# 1_MCU.net
KiCad netlist of a schematic drawn in Altium Designer
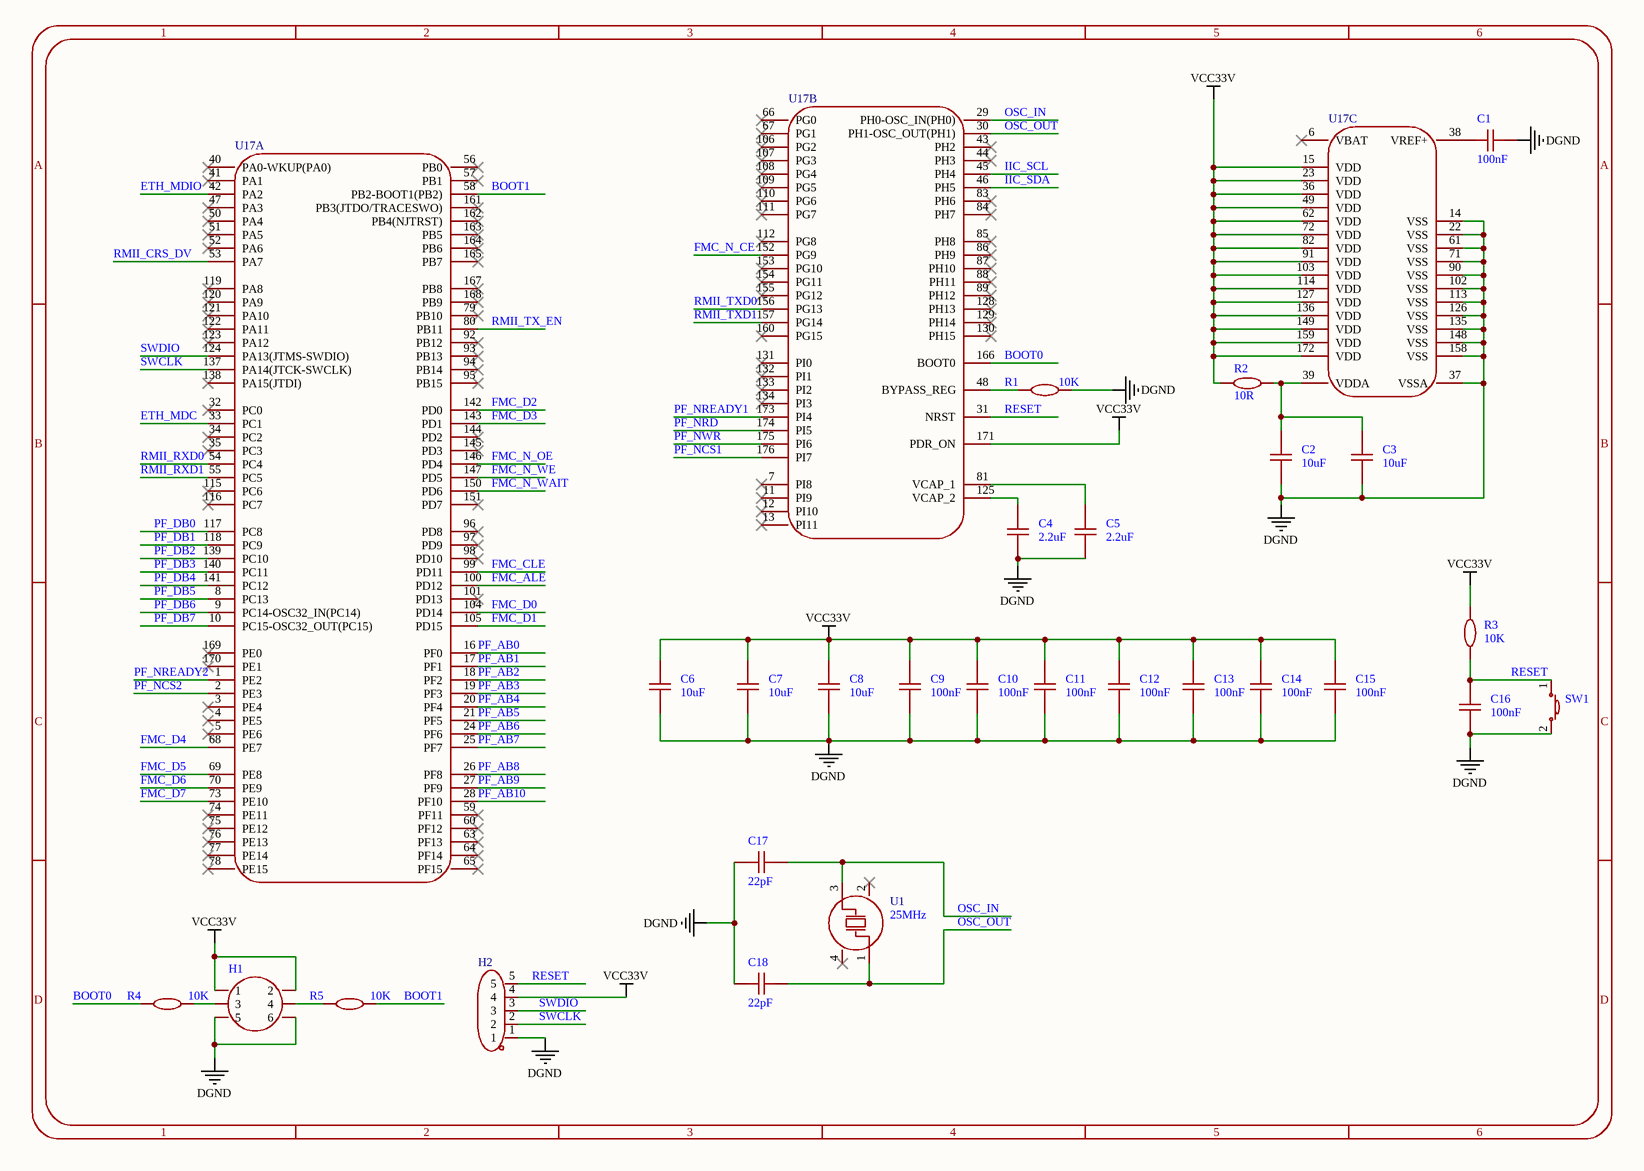
[diagram p0: 1_MCU.schdoc]

(export (version "E")
  (design (tool "Eeschema 10.0.6"))
  (components
    (comp (ref "C1")
      (value "100nF")
      (footprint "C0402")
      (libsource (lib "altium-import") (part "root_2_CAP_0402_"))
    )
    (comp (ref "C2")
      (value "10uF")
      (footprint "C0603")
      (libsource (lib "altium-import") (part "root_1_CAP_0603_"))
    )
    (comp (ref "C3")
      (value "10uF")
      (footprint "C0603")
      (libsource (lib "altium-import") (part "root_1_CAP_0603_"))
    )
    (comp (ref "C4")
      (value "2.2uF")
      (footprint "C0402")
      (libsource (lib "altium-import") (part "root_1_CAP_0402_"))
    )
    (comp (ref "C5")
      (value "2.2uF")
      (footprint "C0402")
      (libsource (lib "altium-import") (part "root_1_CAP_0402_"))
    )
    (comp (ref "C6")
      (value "10uF")
      (footprint "C0603")
      (libsource (lib "altium-import") (part "root_1_CAP_0603_"))
    )
    (comp (ref "C7")
      (value "10uF")
      (footprint "C0603")
      (libsource (lib "altium-import") (part "root_1_CAP_0603_"))
    )
    (comp (ref "C8")
      (value "10uF")
      (footprint "C0603")
      (libsource (lib "altium-import") (part "root_1_CAP_0603_"))
    )
    (comp (ref "C9")
      (value "100nF")
      (footprint "C0402")
      (libsource (lib "altium-import") (part "root_1_CAP_0402_"))
    )
    (comp (ref "C10")
      (value "100nF")
      (footprint "C0402")
      (libsource (lib "altium-import") (part "root_1_CAP_0402_"))
    )
    (comp (ref "C11")
      (value "100nF")
      (footprint "C0402")
      (libsource (lib "altium-import") (part "root_1_CAP_0402_"))
    )
    (comp (ref "C12")
      (value "100nF")
      (footprint "C0402")
      (libsource (lib "altium-import") (part "root_1_CAP_0402_"))
    )
    (comp (ref "C13")
      (value "100nF")
      (footprint "C0402")
      (libsource (lib "altium-import") (part "root_1_CAP_0402_"))
    )
    (comp (ref "C14")
      (value "100nF")
      (footprint "C0402")
      (libsource (lib "altium-import") (part "root_1_CAP_0402_"))
    )
    (comp (ref "C15")
      (value "100nF")
      (footprint "C0402")
      (libsource (lib "altium-import") (part "root_1_CAP_0402_"))
    )
    (comp (ref "C16")
      (value "100nF")
      (footprint "C0402")
      (libsource (lib "altium-import") (part "root_1_CAP_0402_"))
    )
    (comp (ref "C17")
      (value "22pF")
      (footprint "C0402")
      (libsource (lib "altium-import") (part "root_2_CAP_0402_"))
    )
    (comp (ref "C18")
      (value "22pF")
      (footprint "C0402")
      (libsource (lib "altium-import") (part "root_2_CAP_0402_"))
    )
    (comp (ref "H1")
      (value "~")
      (footprint "HDR-TH_6P-P2.54-V-R2-C3-S2.54_A2541WV-2X3P")
      (libsource (lib "altium-import") (part "root_0_HDR-M_2.54_2x3_"))
    )
    (comp (ref "H2")
      (value "~")
      (footprint "HDR-TH_5P-P2.54-V-M")
      (libsource (lib "altium-import") (part "root_2_HDR-M_2.54_1x5P_"))
    )
    (comp (ref "R1")
      (value "10K")
      (footprint "R0402")
      (libsource (lib "altium-import") (part "root_2_Res_0402_"))
    )
    (comp (ref "R2")
      (value "10R")
      (footprint "R0402")
      (libsource (lib "altium-import") (part "root_2_Res_0402_"))
    )
    (comp (ref "R3")
      (value "10K")
      (footprint "R0402")
      (libsource (lib "altium-import") (part "root_1_Res_0402_"))
    )
    (comp (ref "R4")
      (value "10K")
      (footprint "R0402")
      (libsource (lib "altium-import") (part "root_0_Res_0402_"))
    )
    (comp (ref "R5")
      (value "10K")
      (footprint "R0402")
      (libsource (lib "altium-import") (part "root_0_Res_0402_"))
    )
    (comp (ref "SW1")
      (value "~")
      (footprint "Key_SMD_3x4x2")
      (libsource (lib "altium-import") (part "root_3_Key_SMD_3x4x2_"))
    )
    (comp (ref "U1")
      (value "25MHz")
      (footprint "CRYSTAL-SMD_4P-L3.2-W2.5-TR")
      (libsource (lib "altium-import") (part "root_1_25MHz_"))
    )
    (comp (ref "U17")
      (value "~")
      (footprint "LQFP-176_L24.0-W24.0-P0.50-LS26.0-BL")
      (libsource (lib "altium-import") (part "root_0_STM32F429IGT6_"))
    )
  )
  (nets
    (net (code "1") (name "/BOOT0") (class "Default")
      (node (ref "R4") (pin "1") (pinfunction "1_1") (pintype "passive"))
      (node (ref "U17") (pin "166") (pinfunction "BOOT0_166") (pintype "passive"))
    )
    (net (code "2") (name "/BOOT1") (class "Default")
      (node (ref "R5") (pin "2") (pinfunction "2_2") (pintype "passive"))
      (node (ref "U17") (pin "58") (pinfunction "PB2-BOOT1(PB2)_58") (pintype "passive"))
    )
    (net (code "3") (name "/ETH_MDC") (class "Default")
      (node (ref "U17") (pin "33") (pinfunction "PC1_33") (pintype "passive"))
    )
    (net (code "4") (name "/ETH_MDIO") (class "Default")
      (node (ref "U17") (pin "42") (pinfunction "PA2_42") (pintype "passive"))
    )
    (net (code "5") (name "/FMC_ALE") (class "Default")
      (node (ref "U17") (pin "100") (pinfunction "PD12_100") (pintype "passive"))
    )
    (net (code "6") (name "/FMC_CLE") (class "Default")
      (node (ref "U17") (pin "99") (pinfunction "PD11_99") (pintype "passive"))
    )
    (net (code "7") (name "/FMC_D0") (class "Default")
      (node (ref "U17") (pin "104") (pinfunction "PD14_104") (pintype "passive"))
    )
    (net (code "8") (name "/FMC_D1") (class "Default")
      (node (ref "U17") (pin "105") (pinfunction "PD15_105") (pintype "passive"))
    )
    (net (code "9") (name "/FMC_D2") (class "Default")
      (node (ref "U17") (pin "142") (pinfunction "PD0_142") (pintype "passive"))
    )
    (net (code "10") (name "/FMC_D3") (class "Default")
      (node (ref "U17") (pin "143") (pinfunction "PD1_143") (pintype "passive"))
    )
    (net (code "11") (name "/FMC_D4") (class "Default")
      (node (ref "U17") (pin "68") (pinfunction "PE7_68") (pintype "passive"))
    )
    (net (code "12") (name "/FMC_D5") (class "Default")
      (node (ref "U17") (pin "69") (pinfunction "PE8_69") (pintype "passive"))
    )
    (net (code "13") (name "/FMC_D6") (class "Default")
      (node (ref "U17") (pin "70") (pinfunction "PE9_70") (pintype "passive"))
    )
    (net (code "14") (name "/FMC_D7") (class "Default")
      (node (ref "U17") (pin "73") (pinfunction "PE10_73") (pintype "passive"))
    )
    (net (code "15") (name "/FMC_N_CE") (class "Default")
      (node (ref "U17") (pin "152") (pinfunction "PG9_152") (pintype "passive"))
    )
    (net (code "16") (name "/FMC_N_OE") (class "Default")
      (node (ref "U17") (pin "146") (pinfunction "PD4_146") (pintype "passive"))
    )
    (net (code "17") (name "/FMC_N_WAIT") (class "Default")
      (node (ref "U17") (pin "150") (pinfunction "PD6_150") (pintype "passive"))
    )
    (net (code "18") (name "/FMC_N_WE") (class "Default")
      (node (ref "U17") (pin "147") (pinfunction "PD5_147") (pintype "passive"))
    )
    (net (code "19") (name "/IIC_SCL") (class "Default")
      (node (ref "U17") (pin "45") (pinfunction "PH4_45") (pintype "passive"))
    )
    (net (code "20") (name "/IIC_SDA") (class "Default")
      (node (ref "U17") (pin "46") (pinfunction "PH5_46") (pintype "passive"))
    )
    (net (code "21") (name "/OSC_IN") (class "Default")
      (node (ref "C17") (pin "1") (pinfunction "1_1") (pintype "passive"))
      (node (ref "U1") (pin "3") (pinfunction "OSC2_3") (pintype "passive"))
      (node (ref "U17") (pin "29") (pinfunction "PH0-OSC_IN(PH0)_29") (pintype "passive"))
    )
    (net (code "22") (name "/OSC_OUT") (class "Default")
      (node (ref "C18") (pin "1") (pinfunction "1_1") (pintype "passive"))
      (node (ref "U1") (pin "1") (pinfunction "OSC1_1") (pintype "passive"))
      (node (ref "U17") (pin "30") (pinfunction "PH1-OSC_OUT(PH1)_30") (pintype "passive"))
    )
    (net (code "23") (name "/PF_AB0") (class "Default")
      (node (ref "U17") (pin "16") (pinfunction "PF0_16") (pintype "passive"))
    )
    (net (code "24") (name "/PF_AB1") (class "Default")
      (node (ref "U17") (pin "17") (pinfunction "PF1_17") (pintype "passive"))
    )
    (net (code "25") (name "/PF_AB2") (class "Default")
      (node (ref "U17") (pin "18") (pinfunction "PF2_18") (pintype "passive"))
    )
    (net (code "26") (name "/PF_AB3") (class "Default")
      (node (ref "U17") (pin "19") (pinfunction "PF3_19") (pintype "passive"))
    )
    (net (code "27") (name "/PF_AB4") (class "Default")
      (node (ref "U17") (pin "20") (pinfunction "PF4_20") (pintype "passive"))
    )
    (net (code "28") (name "/PF_AB5") (class "Default")
      (node (ref "U17") (pin "21") (pinfunction "PF5_21") (pintype "passive"))
    )
    (net (code "29") (name "/PF_AB6") (class "Default")
      (node (ref "U17") (pin "24") (pinfunction "PF6_24") (pintype "passive"))
    )
    (net (code "30") (name "/PF_AB7") (class "Default")
      (node (ref "U17") (pin "25") (pinfunction "PF7_25") (pintype "passive"))
    )
    (net (code "31") (name "/PF_AB8") (class "Default")
      (node (ref "U17") (pin "26") (pinfunction "PF8_26") (pintype "passive"))
    )
    (net (code "32") (name "/PF_AB9") (class "Default")
      (node (ref "U17") (pin "27") (pinfunction "PF9_27") (pintype "passive"))
    )
    (net (code "33") (name "/PF_AB10") (class "Default")
      (node (ref "U17") (pin "28") (pinfunction "PF10_28") (pintype "passive"))
    )
    (net (code "34") (name "/PF_DB0") (class "Default")
      (node (ref "U17") (pin "117") (pinfunction "PC8_117") (pintype "passive"))
    )
    (net (code "35") (name "/PF_DB1") (class "Default")
      (node (ref "U17") (pin "118") (pinfunction "PC9_118") (pintype "passive"))
    )
    (net (code "36") (name "/PF_DB2") (class "Default")
      (node (ref "U17") (pin "139") (pinfunction "PC10_139") (pintype "passive"))
    )
    (net (code "37") (name "/PF_DB3") (class "Default")
      (node (ref "U17") (pin "140") (pinfunction "PC11_140") (pintype "passive"))
    )
    (net (code "38") (name "/PF_DB4") (class "Default")
      (node (ref "U17") (pin "141") (pinfunction "PC12_141") (pintype "passive"))
    )
    (net (code "39") (name "/PF_DB5") (class "Default")
      (node (ref "U17") (pin "8") (pinfunction "PC13_8") (pintype "passive"))
    )
    (net (code "40") (name "/PF_DB6") (class "Default")
      (node (ref "U17") (pin "9") (pinfunction "PC14-OSC32_IN(PC14)_9") (pintype "passive"))
    )
    (net (code "41") (name "/PF_DB7") (class "Default")
      (node (ref "U17") (pin "10") (pinfunction "PC15-OSC32_OUT(PC15)_10") (pintype "passive"))
    )
    (net (code "42") (name "/PF_NCS1") (class "Default")
      (node (ref "U17") (pin "176") (pinfunction "PI7_176") (pintype "passive"))
    )
    (net (code "43") (name "/PF_NCS2") (class "Default")
      (node (ref "U17") (pin "2") (pinfunction "PE3_2") (pintype "passive"))
    )
    (net (code "44") (name "/PF_NRD") (class "Default")
      (node (ref "U17") (pin "174") (pinfunction "PI5_174") (pintype "passive"))
    )
    (net (code "45") (name "/PF_NREADY1") (class "Default")
      (node (ref "U17") (pin "173") (pinfunction "PI4_173") (pintype "passive"))
    )
    (net (code "46") (name "/PF_NREADY2") (class "Default")
      (node (ref "U17") (pin "1") (pinfunction "PE2_1") (pintype "passive"))
    )
    (net (code "47") (name "/PF_NWR") (class "Default")
      (node (ref "U17") (pin "175") (pinfunction "PI6_175") (pintype "passive"))
    )
    (net (code "48") (name "/RESET") (class "Default")
      (node (ref "C16") (pin "2") (pinfunction "2_2") (pintype "passive"))
      (node (ref "H2") (pin "5") (pinfunction "5_5") (pintype "passive"))
      (node (ref "R3") (pin "1") (pinfunction "1_1") (pintype "passive"))
      (node (ref "SW1") (pin "1") (pinfunction "1_1") (pintype "passive"))
      (node (ref "U17") (pin "31") (pinfunction "NRST_31") (pintype "passive"))
    )
    (net (code "49") (name "/RMII_CRS_DV") (class "Default")
      (node (ref "U17") (pin "53") (pinfunction "PA7_53") (pintype "passive"))
    )
    (net (code "50") (name "/RMII_RXD0") (class "Default")
      (node (ref "U17") (pin "54") (pinfunction "PC4_54") (pintype "passive"))
    )
    (net (code "51") (name "/RMII_RXD1") (class "Default")
      (node (ref "U17") (pin "55") (pinfunction "PC5_55") (pintype "passive"))
    )
    (net (code "52") (name "/RMII_TXD0") (class "Default")
      (node (ref "U17") (pin "156") (pinfunction "PG13_156") (pintype "passive"))
    )
    (net (code "53") (name "/RMII_TXD1") (class "Default")
      (node (ref "U17") (pin "157") (pinfunction "PG14_157") (pintype "passive"))
    )
    (net (code "54") (name "/RMII_TX_EN") (class "Default")
      (node (ref "U17") (pin "80") (pinfunction "PB11_80") (pintype "passive"))
    )
    (net (code "55") (name "/SWCLK") (class "Default")
      (node (ref "H2") (pin "2") (pinfunction "2_2") (pintype "passive"))
      (node (ref "U17") (pin "137") (pinfunction "PA14(JTCK-SWCLK)_137") (pintype "passive"))
    )
    (net (code "56") (name "/SWDIO") (class "Default")
      (node (ref "H2") (pin "3") (pinfunction "3_3") (pintype "passive"))
      (node (ref "U17") (pin "124") (pinfunction "PA13(JTMS-SWDIO)_124") (pintype "passive"))
    )
    (net (code "57") (name "DGND") (class "Default")
      (node (ref "C1") (pin "1") (pinfunction "1_1") (pintype "passive"))
      (node (ref "C10") (pin "1") (pinfunction "1_1") (pintype "passive"))
      (node (ref "C11") (pin "1") (pinfunction "1_1") (pintype "passive"))
      (node (ref "C12") (pin "1") (pinfunction "1_1") (pintype "passive"))
      (node (ref "C13") (pin "1") (pinfunction "1_1") (pintype "passive"))
      (node (ref "C14") (pin "1") (pinfunction "1_1") (pintype "passive"))
      (node (ref "C15") (pin "1") (pinfunction "1_1") (pintype "passive"))
      (node (ref "C16") (pin "1") (pinfunction "1_1") (pintype "passive"))
      (node (ref "C17") (pin "2") (pinfunction "2_2") (pintype "passive"))
      (node (ref "C18") (pin "2") (pinfunction "2_2") (pintype "passive"))
      (node (ref "C2") (pin "1") (pinfunction "1_1") (pintype "passive"))
      (node (ref "C3") (pin "1") (pinfunction "1_1") (pintype "passive"))
      (node (ref "C4") (pin "1") (pinfunction "1_1") (pintype "passive"))
      (node (ref "C5") (pin "1") (pinfunction "1_1") (pintype "passive"))
      (node (ref "C6") (pin "1") (pinfunction "1_1") (pintype "passive"))
      (node (ref "C7") (pin "1") (pinfunction "1_1") (pintype "passive"))
      (node (ref "C8") (pin "1") (pinfunction "1_1") (pintype "passive"))
      (node (ref "C9") (pin "1") (pinfunction "1_1") (pintype "passive"))
      (node (ref "H1") (pin "5") (pinfunction "5_5") (pintype "passive"))
      (node (ref "H1") (pin "6") (pinfunction "6_6") (pintype "passive"))
      (node (ref "H2") (pin "1") (pinfunction "1_1") (pintype "passive"))
      (node (ref "R1") (pin "1") (pinfunction "1_1") (pintype "passive"))
      (node (ref "SW1") (pin "2") (pinfunction "2_2") (pintype "passive"))
      (node (ref "U17") (pin "102") (pinfunction "VSS_102") (pintype "passive"))
      (node (ref "U17") (pin "113") (pinfunction "VSS_113") (pintype "passive"))
      (node (ref "U17") (pin "126") (pinfunction "VSS_126") (pintype "passive"))
      (node (ref "U17") (pin "135") (pinfunction "VSS_135") (pintype "passive"))
      (node (ref "U17") (pin "14") (pinfunction "VSS_14") (pintype "passive"))
      (node (ref "U17") (pin "148") (pinfunction "VSS_148") (pintype "passive"))
      (node (ref "U17") (pin "158") (pinfunction "VSS_158") (pintype "passive"))
      (node (ref "U17") (pin "22") (pinfunction "VSS_22") (pintype "passive"))
      (node (ref "U17") (pin "37") (pinfunction "VSSA_37") (pintype "passive"))
      (node (ref "U17") (pin "61") (pinfunction "VSS_61") (pintype "passive"))
      (node (ref "U17") (pin "71") (pinfunction "VSS_71") (pintype "passive"))
      (node (ref "U17") (pin "90") (pinfunction "VSS_90") (pintype "passive"))
    )
    (net (code "58") (name "Net-(H1-Pad3)") (class "Default")
      (node (ref "H1") (pin "3") (pinfunction "3_3") (pintype "passive"))
      (node (ref "R4") (pin "2") (pinfunction "2_2") (pintype "passive"))
    )
    (net (code "59") (name "Net-(H1-Pad4)") (class "Default")
      (node (ref "H1") (pin "4") (pinfunction "4_4") (pintype "passive"))
      (node (ref "R5") (pin "1") (pinfunction "1_1") (pintype "passive"))
    )
    (net (code "60") (name "Net-(U17B-BYPASS_REG)") (class "Default")
      (node (ref "R1") (pin "2") (pinfunction "2_2") (pintype "passive"))
      (node (ref "U17") (pin "48") (pinfunction "BYPASS_REG_48") (pintype "passive"))
    )
    (net (code "61") (name "Net-(U17B-VCAP_1)") (class "Default")
      (node (ref "C5") (pin "2") (pinfunction "2_2") (pintype "passive"))
      (node (ref "U17") (pin "81") (pinfunction "VCAP_1_81") (pintype "passive"))
    )
    (net (code "62") (name "Net-(U17B-VCAP_2)") (class "Default")
      (node (ref "C4") (pin "2") (pinfunction "2_2") (pintype "passive"))
      (node (ref "U17") (pin "125") (pinfunction "VCAP_2_125") (pintype "passive"))
    )
    (net (code "63") (name "Net-(U17C-VDDA)") (class "Default")
      (node (ref "C2") (pin "2") (pinfunction "2_2") (pintype "passive"))
      (node (ref "C3") (pin "2") (pinfunction "2_2") (pintype "passive"))
      (node (ref "R2") (pin "1") (pinfunction "1_1") (pintype "passive"))
      (node (ref "U17") (pin "39") (pinfunction "VDDA_39") (pintype "passive"))
    )
    (net (code "64") (name "Net-(U17C-VREF+)") (class "Default")
      (node (ref "C1") (pin "2") (pinfunction "2_2") (pintype "passive"))
      (node (ref "U17") (pin "38") (pinfunction "VREF+_38") (pintype "passive"))
    )
    (net (code "65") (name "VCC33V") (class "Default")
      (node (ref "C10") (pin "2") (pinfunction "2_2") (pintype "passive"))
      (node (ref "C11") (pin "2") (pinfunction "2_2") (pintype "passive"))
      (node (ref "C12") (pin "2") (pinfunction "2_2") (pintype "passive"))
      (node (ref "C13") (pin "2") (pinfunction "2_2") (pintype "passive"))
      (node (ref "C14") (pin "2") (pinfunction "2_2") (pintype "passive"))
      (node (ref "C15") (pin "2") (pinfunction "2_2") (pintype "passive"))
      (node (ref "C6") (pin "2") (pinfunction "2_2") (pintype "passive"))
      (node (ref "C7") (pin "2") (pinfunction "2_2") (pintype "passive"))
      (node (ref "C8") (pin "2") (pinfunction "2_2") (pintype "passive"))
      (node (ref "C9") (pin "2") (pinfunction "2_2") (pintype "passive"))
      (node (ref "H1") (pin "1") (pinfunction "1_1") (pintype "passive"))
      (node (ref "H1") (pin "2") (pinfunction "2_2") (pintype "passive"))
      (node (ref "H2") (pin "4") (pinfunction "4_4") (pintype "passive"))
      (node (ref "R2") (pin "2") (pinfunction "2_2") (pintype "passive"))
      (node (ref "R3") (pin "2") (pinfunction "2_2") (pintype "passive"))
      (node (ref "U17") (pin "103") (pinfunction "VDD_103") (pintype "passive"))
      (node (ref "U17") (pin "114") (pinfunction "VDD_114") (pintype "passive"))
      (node (ref "U17") (pin "127") (pinfunction "VDD_127") (pintype "passive"))
      (node (ref "U17") (pin "136") (pinfunction "VDD_136") (pintype "passive"))
      (node (ref "U17") (pin "149") (pinfunction "VDD_149") (pintype "passive"))
      (node (ref "U17") (pin "15") (pinfunction "VDD_15") (pintype "passive"))
      (node (ref "U17") (pin "159") (pinfunction "VDD_159") (pintype "passive"))
      (node (ref "U17") (pin "171") (pinfunction "PDR_ON_171") (pintype "passive"))
      (node (ref "U17") (pin "172") (pinfunction "VDD_172") (pintype "passive"))
      (node (ref "U17") (pin "23") (pinfunction "VDD_23") (pintype "passive"))
      (node (ref "U17") (pin "36") (pinfunction "VDD_36") (pintype "passive"))
      (node (ref "U17") (pin "49") (pinfunction "VDD_49") (pintype "passive"))
      (node (ref "U17") (pin "62") (pinfunction "VDD_62") (pintype "passive"))
      (node (ref "U17") (pin "72") (pinfunction "VDD_72") (pintype "passive"))
      (node (ref "U17") (pin "82") (pinfunction "VDD_82") (pintype "passive"))
      (node (ref "U17") (pin "91") (pinfunction "VDD_91") (pintype "passive"))
    )
    (net (code "66") (name "unconnected-(U1-GND-Pad2)") (class "Default")
      (node (ref "U1") (pin "2") (pinfunction "GND_2") (pintype "passive+no_connect"))
    )
    (net (code "67") (name "unconnected-(U1-GND-Pad4)") (class "Default")
      (node (ref "U1") (pin "4") (pinfunction "GND_4") (pintype "passive+no_connect"))
    )
    (net (code "68") (name "unconnected-(U17A-PA0-WKUP(PA0)-Pad40)") (class "Default")
      (node (ref "U17") (pin "40") (pinfunction "PA0-WKUP(PA0)_40") (pintype "passive+no_connect"))
    )
    (net (code "69") (name "unconnected-(U17A-PA1-Pad41)") (class "Default")
      (node (ref "U17") (pin "41") (pinfunction "PA1_41") (pintype "passive+no_connect"))
    )
    (net (code "70") (name "unconnected-(U17A-PA3-Pad47)") (class "Default")
      (node (ref "U17") (pin "47") (pinfunction "PA3_47") (pintype "passive+no_connect"))
    )
    (net (code "71") (name "unconnected-(U17A-PA4-Pad50)") (class "Default")
      (node (ref "U17") (pin "50") (pinfunction "PA4_50") (pintype "passive+no_connect"))
    )
    (net (code "72") (name "unconnected-(U17A-PA5-Pad51)") (class "Default")
      (node (ref "U17") (pin "51") (pinfunction "PA5_51") (pintype "passive+no_connect"))
    )
    (net (code "73") (name "unconnected-(U17A-PA6-Pad52)") (class "Default")
      (node (ref "U17") (pin "52") (pinfunction "PA6_52") (pintype "passive+no_connect"))
    )
    (net (code "74") (name "unconnected-(U17A-PA8-Pad119)") (class "Default")
      (node (ref "U17") (pin "119") (pinfunction "PA8_119") (pintype "passive+no_connect"))
    )
    (net (code "75") (name "unconnected-(U17A-PA9-Pad120)") (class "Default")
      (node (ref "U17") (pin "120") (pinfunction "PA9_120") (pintype "passive+no_connect"))
    )
    (net (code "76") (name "unconnected-(U17A-PA10-Pad121)") (class "Default")
      (node (ref "U17") (pin "121") (pinfunction "PA10_121") (pintype "passive+no_connect"))
    )
    (net (code "77") (name "unconnected-(U17A-PA11-Pad122)") (class "Default")
      (node (ref "U17") (pin "122") (pinfunction "PA11_122") (pintype "passive+no_connect"))
    )
    (net (code "78") (name "unconnected-(U17A-PA12-Pad123)") (class "Default")
      (node (ref "U17") (pin "123") (pinfunction "PA12_123") (pintype "passive+no_connect"))
    )
    (net (code "79") (name "unconnected-(U17A-PA15(JTDI)-Pad138)") (class "Default")
      (node (ref "U17") (pin "138") (pinfunction "PA15(JTDI)_138") (pintype "passive+no_connect"))
    )
    (net (code "80") (name "unconnected-(U17A-PB0-Pad56)") (class "Default")
      (node (ref "U17") (pin "56") (pinfunction "PB0_56") (pintype "passive+no_connect"))
    )
    (net (code "81") (name "unconnected-(U17A-PB1-Pad57)") (class "Default")
      (node (ref "U17") (pin "57") (pinfunction "PB1_57") (pintype "passive+no_connect"))
    )
    (net (code "82") (name "unconnected-(U17A-PB3(JTDO{slash}TRACESWO)-Pad161)") (class "Default")
      (node (ref "U17") (pin "161") (pinfunction "PB3(JTDO/TRACESWO)_161") (pintype "passive+no_connect"))
    )
    (net (code "83") (name "unconnected-(U17A-PB4(NJTRST)-Pad162)") (class "Default")
      (node (ref "U17") (pin "162") (pinfunction "PB4(NJTRST)_162") (pintype "passive+no_connect"))
    )
    (net (code "84") (name "unconnected-(U17A-PB5-Pad163)") (class "Default")
      (node (ref "U17") (pin "163") (pinfunction "PB5_163") (pintype "passive+no_connect"))
    )
    (net (code "85") (name "unconnected-(U17A-PB6-Pad164)") (class "Default")
      (node (ref "U17") (pin "164") (pinfunction "PB6_164") (pintype "passive+no_connect"))
    )
    (net (code "86") (name "unconnected-(U17A-PB7-Pad165)") (class "Default")
      (node (ref "U17") (pin "165") (pinfunction "PB7_165") (pintype "passive+no_connect"))
    )
    (net (code "87") (name "unconnected-(U17A-PB8-Pad167)") (class "Default")
      (node (ref "U17") (pin "167") (pinfunction "PB8_167") (pintype "passive+no_connect"))
    )
    (net (code "88") (name "unconnected-(U17A-PB9-Pad168)") (class "Default")
      (node (ref "U17") (pin "168") (pinfunction "PB9_168") (pintype "passive+no_connect"))
    )
    (net (code "89") (name "unconnected-(U17A-PB10-Pad79)") (class "Default")
      (node (ref "U17") (pin "79") (pinfunction "PB10_79") (pintype "passive+no_connect"))
    )
    (net (code "90") (name "unconnected-(U17A-PB12-Pad92)") (class "Default")
      (node (ref "U17") (pin "92") (pinfunction "PB12_92") (pintype "passive+no_connect"))
    )
    (net (code "91") (name "unconnected-(U17A-PB13-Pad93)") (class "Default")
      (node (ref "U17") (pin "93") (pinfunction "PB13_93") (pintype "passive+no_connect"))
    )
    (net (code "92") (name "unconnected-(U17A-PB14-Pad94)") (class "Default")
      (node (ref "U17") (pin "94") (pinfunction "PB14_94") (pintype "passive+no_connect"))
    )
    (net (code "93") (name "unconnected-(U17A-PB15-Pad95)") (class "Default")
      (node (ref "U17") (pin "95") (pinfunction "PB15_95") (pintype "passive+no_connect"))
    )
    (net (code "94") (name "unconnected-(U17A-PC0-Pad32)") (class "Default")
      (node (ref "U17") (pin "32") (pinfunction "PC0_32") (pintype "passive+no_connect"))
    )
    (net (code "95") (name "unconnected-(U17A-PC2-Pad34)") (class "Default")
      (node (ref "U17") (pin "34") (pinfunction "PC2_34") (pintype "passive+no_connect"))
    )
    (net (code "96") (name "unconnected-(U17A-PC3-Pad35)") (class "Default")
      (node (ref "U17") (pin "35") (pinfunction "PC3_35") (pintype "passive+no_connect"))
    )
    (net (code "97") (name "unconnected-(U17A-PC6-Pad115)") (class "Default")
      (node (ref "U17") (pin "115") (pinfunction "PC6_115") (pintype "passive+no_connect"))
    )
    (net (code "98") (name "unconnected-(U17A-PC7-Pad116)") (class "Default")
      (node (ref "U17") (pin "116") (pinfunction "PC7_116") (pintype "passive+no_connect"))
    )
    (net (code "99") (name "unconnected-(U17A-PD2-Pad144)") (class "Default")
      (node (ref "U17") (pin "144") (pinfunction "PD2_144") (pintype "passive+no_connect"))
    )
    (net (code "100") (name "unconnected-(U17A-PD3-Pad145)") (class "Default")
      (node (ref "U17") (pin "145") (pinfunction "PD3_145") (pintype "passive+no_connect"))
    )
    (net (code "101") (name "unconnected-(U17A-PD7-Pad151)") (class "Default")
      (node (ref "U17") (pin "151") (pinfunction "PD7_151") (pintype "passive+no_connect"))
    )
    (net (code "102") (name "unconnected-(U17A-PD8-Pad96)") (class "Default")
      (node (ref "U17") (pin "96") (pinfunction "PD8_96") (pintype "passive+no_connect"))
    )
    (net (code "103") (name "unconnected-(U17A-PD9-Pad97)") (class "Default")
      (node (ref "U17") (pin "97") (pinfunction "PD9_97") (pintype "passive+no_connect"))
    )
    (net (code "104") (name "unconnected-(U17A-PD10-Pad98)") (class "Default")
      (node (ref "U17") (pin "98") (pinfunction "PD10_98") (pintype "passive+no_connect"))
    )
    (net (code "105") (name "unconnected-(U17A-PD13-Pad101)") (class "Default")
      (node (ref "U17") (pin "101") (pinfunction "PD13_101") (pintype "passive+no_connect"))
    )
    (net (code "106") (name "unconnected-(U17A-PE0-Pad169)") (class "Default")
      (node (ref "U17") (pin "169") (pinfunction "PE0_169") (pintype "passive+no_connect"))
    )
    (net (code "107") (name "unconnected-(U17A-PE1-Pad170)") (class "Default")
      (node (ref "U17") (pin "170") (pinfunction "PE1_170") (pintype "passive+no_connect"))
    )
    (net (code "108") (name "unconnected-(U17A-PE4-Pad3)") (class "Default")
      (node (ref "U17") (pin "3") (pinfunction "PE4_3") (pintype "passive+no_connect"))
    )
    (net (code "109") (name "unconnected-(U17A-PE5-Pad4)") (class "Default")
      (node (ref "U17") (pin "4") (pinfunction "PE5_4") (pintype "passive+no_connect"))
    )
    (net (code "110") (name "unconnected-(U17A-PE6-Pad5)") (class "Default")
      (node (ref "U17") (pin "5") (pinfunction "PE6_5") (pintype "passive+no_connect"))
    )
    (net (code "111") (name "unconnected-(U17A-PE11-Pad74)") (class "Default")
      (node (ref "U17") (pin "74") (pinfunction "PE11_74") (pintype "passive+no_connect"))
    )
    (net (code "112") (name "unconnected-(U17A-PE12-Pad75)") (class "Default")
      (node (ref "U17") (pin "75") (pinfunction "PE12_75") (pintype "passive+no_connect"))
    )
    (net (code "113") (name "unconnected-(U17A-PE13-Pad76)") (class "Default")
      (node (ref "U17") (pin "76") (pinfunction "PE13_76") (pintype "passive+no_connect"))
    )
    (net (code "114") (name "unconnected-(U17A-PE14-Pad77)") (class "Default")
      (node (ref "U17") (pin "77") (pinfunction "PE14_77") (pintype "passive+no_connect"))
    )
    (net (code "115") (name "unconnected-(U17A-PE15-Pad78)") (class "Default")
      (node (ref "U17") (pin "78") (pinfunction "PE15_78") (pintype "passive+no_connect"))
    )
    (net (code "116") (name "unconnected-(U17A-PF11-Pad59)") (class "Default")
      (node (ref "U17") (pin "59") (pinfunction "PF11_59") (pintype "passive+no_connect"))
    )
    (net (code "117") (name "unconnected-(U17A-PF12-Pad60)") (class "Default")
      (node (ref "U17") (pin "60") (pinfunction "PF12_60") (pintype "passive+no_connect"))
    )
    (net (code "118") (name "unconnected-(U17A-PF13-Pad63)") (class "Default")
      (node (ref "U17") (pin "63") (pinfunction "PF13_63") (pintype "passive+no_connect"))
    )
    (net (code "119") (name "unconnected-(U17A-PF14-Pad64)") (class "Default")
      (node (ref "U17") (pin "64") (pinfunction "PF14_64") (pintype "passive+no_connect"))
    )
    (net (code "120") (name "unconnected-(U17A-PF15-Pad65)") (class "Default")
      (node (ref "U17") (pin "65") (pinfunction "PF15_65") (pintype "passive+no_connect"))
    )
    (net (code "121") (name "unconnected-(U17B-PG0-Pad66)") (class "Default")
      (node (ref "U17") (pin "66") (pinfunction "PG0_66") (pintype "passive+no_connect"))
    )
    (net (code "122") (name "unconnected-(U17B-PG1-Pad67)") (class "Default")
      (node (ref "U17") (pin "67") (pinfunction "PG1_67") (pintype "passive+no_connect"))
    )
    (net (code "123") (name "unconnected-(U17B-PG2-Pad106)") (class "Default")
      (node (ref "U17") (pin "106") (pinfunction "PG2_106") (pintype "passive+no_connect"))
    )
    (net (code "124") (name "unconnected-(U17B-PG3-Pad107)") (class "Default")
      (node (ref "U17") (pin "107") (pinfunction "PG3_107") (pintype "passive+no_connect"))
    )
    (net (code "125") (name "unconnected-(U17B-PG4-Pad108)") (class "Default")
      (node (ref "U17") (pin "108") (pinfunction "PG4_108") (pintype "passive+no_connect"))
    )
    (net (code "126") (name "unconnected-(U17B-PG5-Pad109)") (class "Default")
      (node (ref "U17") (pin "109") (pinfunction "PG5_109") (pintype "passive+no_connect"))
    )
    (net (code "127") (name "unconnected-(U17B-PG6-Pad110)") (class "Default")
      (node (ref "U17") (pin "110") (pinfunction "PG6_110") (pintype "passive+no_connect"))
    )
    (net (code "128") (name "unconnected-(U17B-PG7-Pad111)") (class "Default")
      (node (ref "U17") (pin "111") (pinfunction "PG7_111") (pintype "passive+no_connect"))
    )
    (net (code "129") (name "unconnected-(U17B-PG8-Pad112)") (class "Default")
      (node (ref "U17") (pin "112") (pinfunction "PG8_112") (pintype "passive+no_connect"))
    )
    (net (code "130") (name "unconnected-(U17B-PG10-Pad153)") (class "Default")
      (node (ref "U17") (pin "153") (pinfunction "PG10_153") (pintype "passive+no_connect"))
    )
    (net (code "131") (name "unconnected-(U17B-PG11-Pad154)") (class "Default")
      (node (ref "U17") (pin "154") (pinfunction "PG11_154") (pintype "passive+no_connect"))
    )
    (net (code "132") (name "unconnected-(U17B-PG12-Pad155)") (class "Default")
      (node (ref "U17") (pin "155") (pinfunction "PG12_155") (pintype "passive+no_connect"))
    )
    (net (code "133") (name "unconnected-(U17B-PG15-Pad160)") (class "Default")
      (node (ref "U17") (pin "160") (pinfunction "PG15_160") (pintype "passive+no_connect"))
    )
    (net (code "134") (name "unconnected-(U17B-PH2-Pad43)") (class "Default")
      (node (ref "U17") (pin "43") (pinfunction "PH2_43") (pintype "passive+no_connect"))
    )
    (net (code "135") (name "unconnected-(U17B-PH3-Pad44)") (class "Default")
      (node (ref "U17") (pin "44") (pinfunction "PH3_44") (pintype "passive+no_connect"))
    )
    (net (code "136") (name "unconnected-(U17B-PH6-Pad83)") (class "Default")
      (node (ref "U17") (pin "83") (pinfunction "PH6_83") (pintype "passive+no_connect"))
    )
    (net (code "137") (name "unconnected-(U17B-PH7-Pad84)") (class "Default")
      (node (ref "U17") (pin "84") (pinfunction "PH7_84") (pintype "passive+no_connect"))
    )
    (net (code "138") (name "unconnected-(U17B-PH8-Pad85)") (class "Default")
      (node (ref "U17") (pin "85") (pinfunction "PH8_85") (pintype "passive+no_connect"))
    )
    (net (code "139") (name "unconnected-(U17B-PH9-Pad86)") (class "Default")
      (node (ref "U17") (pin "86") (pinfunction "PH9_86") (pintype "passive+no_connect"))
    )
    (net (code "140") (name "unconnected-(U17B-PH10-Pad87)") (class "Default")
      (node (ref "U17") (pin "87") (pinfunction "PH10_87") (pintype "passive+no_connect"))
    )
    (net (code "141") (name "unconnected-(U17B-PH11-Pad88)") (class "Default")
      (node (ref "U17") (pin "88") (pinfunction "PH11_88") (pintype "passive+no_connect"))
    )
    (net (code "142") (name "unconnected-(U17B-PH12-Pad89)") (class "Default")
      (node (ref "U17") (pin "89") (pinfunction "PH12_89") (pintype "passive+no_connect"))
    )
    (net (code "143") (name "unconnected-(U17B-PH13-Pad128)") (class "Default")
      (node (ref "U17") (pin "128") (pinfunction "PH13_128") (pintype "passive+no_connect"))
    )
    (net (code "144") (name "unconnected-(U17B-PH14-Pad129)") (class "Default")
      (node (ref "U17") (pin "129") (pinfunction "PH14_129") (pintype "passive+no_connect"))
    )
    (net (code "145") (name "unconnected-(U17B-PH15-Pad130)") (class "Default")
      (node (ref "U17") (pin "130") (pinfunction "PH15_130") (pintype "passive+no_connect"))
    )
    (net (code "146") (name "unconnected-(U17B-PI0-Pad131)") (class "Default")
      (node (ref "U17") (pin "131") (pinfunction "PI0_131") (pintype "passive+no_connect"))
    )
    (net (code "147") (name "unconnected-(U17B-PI1-Pad132)") (class "Default")
      (node (ref "U17") (pin "132") (pinfunction "PI1_132") (pintype "passive+no_connect"))
    )
    (net (code "148") (name "unconnected-(U17B-PI2-Pad133)") (class "Default")
      (node (ref "U17") (pin "133") (pinfunction "PI2_133") (pintype "passive+no_connect"))
    )
    (net (code "149") (name "unconnected-(U17B-PI3-Pad134)") (class "Default")
      (node (ref "U17") (pin "134") (pinfunction "PI3_134") (pintype "passive+no_connect"))
    )
    (net (code "150") (name "unconnected-(U17B-PI8-Pad7)") (class "Default")
      (node (ref "U17") (pin "7") (pinfunction "PI8_7") (pintype "passive+no_connect"))
    )
    (net (code "151") (name "unconnected-(U17B-PI9-Pad11)") (class "Default")
      (node (ref "U17") (pin "11") (pinfunction "PI9_11") (pintype "passive+no_connect"))
    )
    (net (code "152") (name "unconnected-(U17B-PI10-Pad12)") (class "Default")
      (node (ref "U17") (pin "12") (pinfunction "PI10_12") (pintype "passive+no_connect"))
    )
    (net (code "153") (name "unconnected-(U17B-PI11-Pad13)") (class "Default")
      (node (ref "U17") (pin "13") (pinfunction "PI11_13") (pintype "passive+no_connect"))
    )
    (net (code "154") (name "unconnected-(U17C-VBAT-Pad6)") (class "Default")
      (node (ref "U17") (pin "6") (pinfunction "VBAT_6") (pintype "passive+no_connect"))
    )
  )
)
